# Sensor_Board.net
KiCad netlist of a schematic drawn in EAGLE
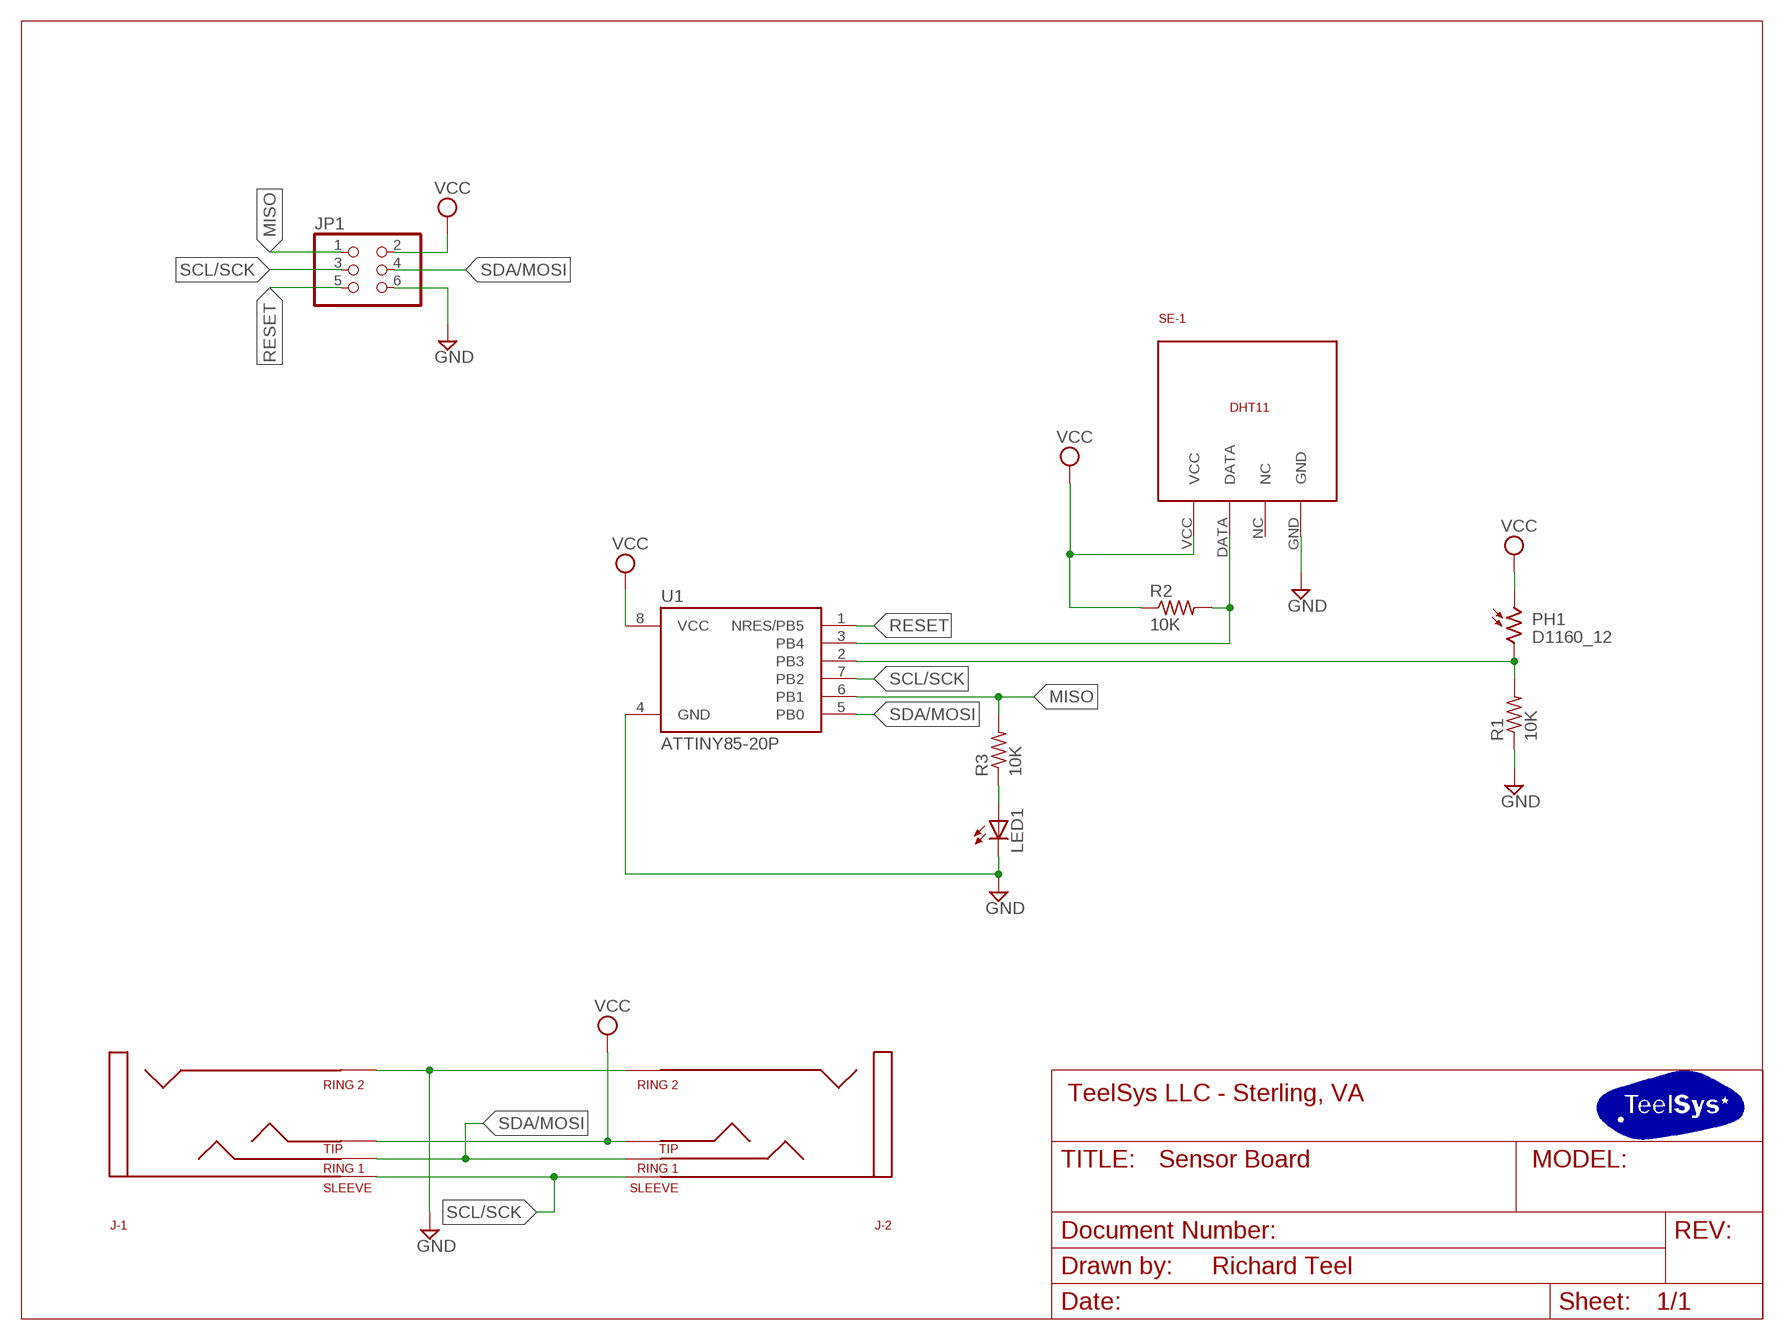
[diagram p0: schematic, sheet 1]

(export (version "E")
  (design (tool "Eeschema 10.0.6"))
  (components
    (comp (ref "J-1")
      (value "4POLE_AUDIO_JACK")
      (footprint "eagle-import:4POLE_AUDIO_JACK")
      (libsource (lib "eagle-import") (part "4POLE_AUDIO_JACK"))
    )
    (comp (ref "J-2")
      (value "4POLE_AUDIO_JACK")
      (footprint "eagle-import:4POLE_AUDIO_JACK")
      (libsource (lib "eagle-import") (part "4POLE_AUDIO_JACK"))
    )
    (comp (ref "JP1")
      (value "PINHD-2X3")
      (footprint "eagle-import:2X03")
      (libsource (lib "eagle-import") (part "PINHD-2X3"))
    )
    (comp (ref "LED1")
      (value "LED5MM")
      (footprint "eagle-import:LED5MM")
      (libsource (lib "eagle-import") (part "LED5MM"))
    )
    (comp (ref "PH1")
      (value "D1160_12")
      (footprint "eagle-import:D11XX")
      (libsource (lib "eagle-import") (part "D1160_12"))
    )
    (comp (ref "R1")
      (value "10K")
      (footprint "eagle-import:0805-THM")
      (libsource (lib "eagle-import") (part "R-US_FLIPFLOP"))
    )
    (comp (ref "R2")
      (value "10K")
      (footprint "eagle-import:0805-THM")
      (libsource (lib "eagle-import") (part "R-US_FLIPFLOP"))
    )
    (comp (ref "R3")
      (value "10K")
      (footprint "eagle-import:0805-THM")
      (libsource (lib "eagle-import") (part "R-US_FLIPFLOP"))
    )
    (comp (ref "SE-1")
      (value "DHT11THROUGH_HOLE")
      (footprint "eagle-import:DHT11")
      (libsource (lib "eagle-import") (part "DHT11THROUGH_HOLE"))
    )
    (comp (ref "U1")
      (value "ATTINY85-20P")
      (footprint "eagle-import:PDIP08_300MIL")
      (libsource (lib "eagle-import") (part "ATTINY85P-20"))
    )
  )
  (nets
    (net (code "1") (name "GND") (class "Default")
      (node (ref "J-1") (pin "RING2") (pinfunction "RING2_RING2") (pintype "bidirectional"))
      (node (ref "J-2") (pin "RING2") (pinfunction "RING2_RING2") (pintype "bidirectional"))
      (node (ref "JP1") (pin "6") (pinfunction "6_6") (pintype "passive"))
      (node (ref "LED1") (pin "K") (pinfunction "C_K") (pintype "passive"))
      (node (ref "R1") (pin "1") (pinfunction "1_1") (pintype "passive"))
      (node (ref "SE-1") (pin "GND") (pinfunction "GND_GND") (pintype "bidirectional"))
      (node (ref "U1") (pin "4") (pinfunction "GND_4") (pintype "power_in"))
    )
    (net (code "2") (name "MISO") (class "Default")
      (node (ref "JP1") (pin "1") (pinfunction "1_1") (pintype "passive"))
      (node (ref "R3") (pin "2") (pinfunction "2_2") (pintype "passive"))
      (node (ref "U1") (pin "6") (pinfunction "PB1_6") (pintype "bidirectional"))
    )
    (net (code "3") (name "Net-(LED1-PadA)") (class "Default")
      (node (ref "LED1") (pin "A") (pinfunction "A_A") (pintype "passive"))
      (node (ref "R3") (pin "1") (pinfunction "1_1") (pintype "passive"))
    )
    (net (code "4") (name "Net-(U1-PB3)") (class "Default")
      (node (ref "PH1") (pin "2") (pinfunction "2_2") (pintype "passive"))
      (node (ref "R1") (pin "2") (pinfunction "2_2") (pintype "passive"))
      (node (ref "U1") (pin "2") (pinfunction "PB3_2") (pintype "bidirectional"))
    )
    (net (code "5") (name "Net-(U1-PB4)") (class "Default")
      (node (ref "R2") (pin "2") (pinfunction "2_2") (pintype "passive"))
      (node (ref "SE-1") (pin "DATA") (pinfunction "DATA_DATA") (pintype "bidirectional"))
      (node (ref "U1") (pin "3") (pinfunction "PB4_3") (pintype "bidirectional"))
    )
    (net (code "6") (name "RESET") (class "Default")
      (node (ref "JP1") (pin "5") (pinfunction "5_5") (pintype "passive"))
      (node (ref "U1") (pin "1") (pinfunction "NRES/PB5_1") (pintype "bidirectional"))
    )
    (net (code "7") (name "SCL{slash}SCK") (class "Default")
      (node (ref "J-1") (pin "SLEEVE") (pinfunction "SLEEVE_SLEEVE") (pintype "bidirectional"))
      (node (ref "J-2") (pin "SLEEVE") (pinfunction "SLEEVE_SLEEVE") (pintype "bidirectional"))
      (node (ref "JP1") (pin "3") (pinfunction "3_3") (pintype "passive"))
      (node (ref "U1") (pin "7") (pinfunction "PB2_7") (pintype "bidirectional"))
    )
    (net (code "8") (name "SDA{slash}MOSI") (class "Default")
      (node (ref "J-1") (pin "RING1") (pinfunction "RING1_RING1") (pintype "bidirectional"))
      (node (ref "J-2") (pin "RING1") (pinfunction "RING1_RING1") (pintype "bidirectional"))
      (node (ref "JP1") (pin "4") (pinfunction "4_4") (pintype "passive"))
      (node (ref "U1") (pin "5") (pinfunction "PB0_5") (pintype "bidirectional"))
    )
    (net (code "9") (name "VCC") (class "Default")
      (node (ref "J-1") (pin "TIP1") (pinfunction "TIP_TIP1") (pintype "bidirectional"))
      (node (ref "J-2") (pin "TIP1") (pinfunction "TIP_TIP1") (pintype "bidirectional"))
      (node (ref "JP1") (pin "2") (pinfunction "2_2") (pintype "passive"))
      (node (ref "PH1") (pin "1") (pinfunction "1_1") (pintype "passive"))
      (node (ref "R2") (pin "1") (pinfunction "1_1") (pintype "passive"))
      (node (ref "SE-1") (pin "VCC") (pinfunction "VCC_VCC") (pintype "bidirectional"))
      (node (ref "U1") (pin "8") (pinfunction "VCC_8") (pintype "power_in"))
    )
    (net (code "10") (name "unconnected-(SE-1-PadNC)") (class "Default")
      (node (ref "SE-1") (pin "NC") (pinfunction "NC_NC") (pintype "bidirectional"))
    )
  )
)
